# headstage-programmer.net
KiCad netlist of a schematic drawn in EAGLE
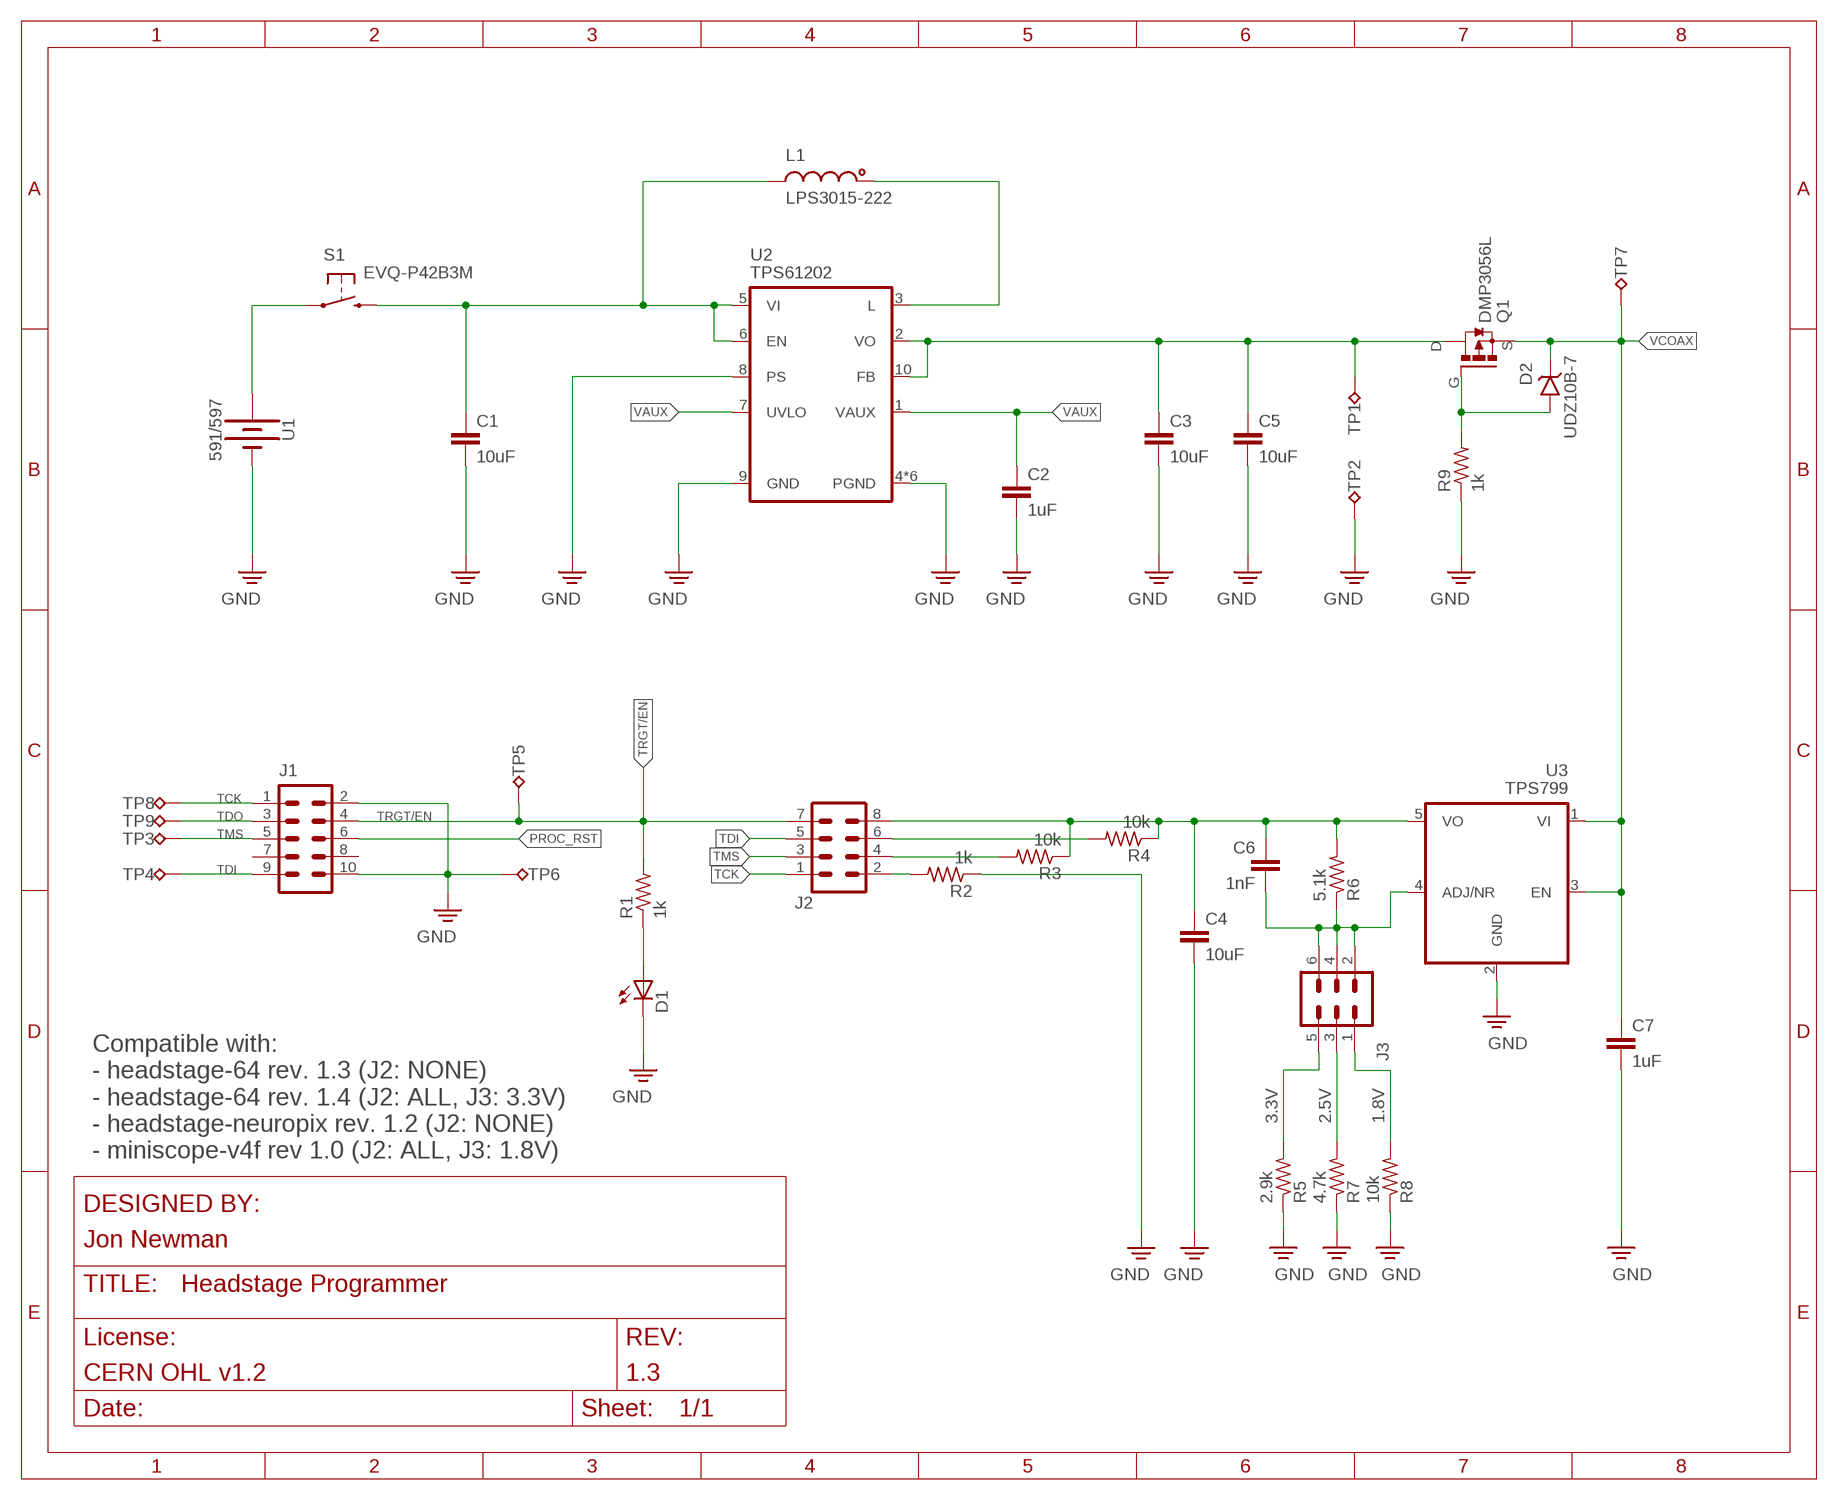
[diagram p0: schematic, sheet 1]

(export (version "E")
  (design (tool "Eeschema 10.0.6"))
  (components
    (comp (ref "C1")
      (value "10uF")
      (footprint "eagle-import:0805")
      (fields (field (name "PARTNO") "C2012X5R1Cxxxxxxx"))
      (libsource (lib "eagle-import") (part "C_0805"))
    )
    (comp (ref "C2")
      (value "1uF")
      (footprint "eagle-import:0603")
      (libsource (lib "eagle-import") (part "C_0603"))
    )
    (comp (ref "C3")
      (value "10uF")
      (footprint "eagle-import:0805")
      (fields (field (name "PARTNO") "C2012X5R1Cxxxxxxx"))
      (libsource (lib "eagle-import") (part "C_0805"))
    )
    (comp (ref "C4")
      (value "10uF")
      (footprint "eagle-import:0805")
      (fields (field (name "PARTNO") "C2012X5R1Cxxxxxxx"))
      (libsource (lib "eagle-import") (part "C_0805"))
    )
    (comp (ref "C5")
      (value "10uF")
      (footprint "eagle-import:0805")
      (fields (field (name "PARTNO") "C2012X5R1Cxxxxxxx"))
      (libsource (lib "eagle-import") (part "C_0805"))
    )
    (comp (ref "C6")
      (value "1nF")
      (footprint "eagle-import:0402")
      (libsource (lib "eagle-import") (part "C_0402"))
    )
    (comp (ref "C7")
      (value "1uF")
      (footprint "eagle-import:0603")
      (libsource (lib "eagle-import") (part "C_0603"))
    )
    (comp (ref "D1")
      (value "LED_0603")
      (footprint "eagle-import:LED-0603")
      (libsource (lib "eagle-import") (part "LED_0603"))
    )
    (comp (ref "D2")
      (value "UDZ10B-7")
      (footprint "eagle-import:SOD-323")
      (libsource (lib "eagle-import") (part "Z-DIODE_SOD-323"))
    )
    (comp (ref "J1")
      (value "302-S101")
      (footprint "eagle-import:2X05_IDC")
      (libsource (lib "eagle-import") (part "PINHD-2X5_IDC"))
    )
    (comp (ref "J2")
      (value "PINHD-2X4_0.05\"")
      (footprint "eagle-import:2X04-0.05_")
      (libsource (lib "eagle-import") (part "PINHD-2X4_0.05{dblquote}"))
    )
    (comp (ref "J3")
      (value "PINHD-2X3_0.05\"")
      (footprint "eagle-import:2X03-0.05_")
      (libsource (lib "eagle-import") (part "PINHD-2X3_0.05{dblquote}"))
    )
    (comp (ref "L1")
      (value "LPS3015-222")
      (footprint "eagle-import:LPS3015")
      (libsource (lib "eagle-import") (part "L_LPS3015"))
    )
    (comp (ref "Q1")
      (value "DMP3056L")
      (footprint "eagle-import:SOT23-GSD")
      (fields (field (name "PARTNO") "DMP3056L-7"))
      (libsource (lib "eagle-import") (part "P-MOSFET_SOT23-GSD"))
    )
    (comp (ref "R1")
      (value "1k")
      (footprint "eagle-import:0402")
      (libsource (lib "eagle-import") (part "R_0402"))
    )
    (comp (ref "R2")
      (value "1k")
      (footprint "eagle-import:0402")
      (libsource (lib "eagle-import") (part "R_0402"))
    )
    (comp (ref "R3")
      (value "10k")
      (footprint "eagle-import:0402")
      (libsource (lib "eagle-import") (part "R_0402"))
    )
    (comp (ref "R4")
      (value "10k")
      (footprint "eagle-import:0402")
      (libsource (lib "eagle-import") (part "R_0402"))
    )
    (comp (ref "R5")
      (value "2.9k")
      (footprint "eagle-import:0402")
      (libsource (lib "eagle-import") (part "R_0402"))
    )
    (comp (ref "R6")
      (value "5.1k")
      (footprint "eagle-import:0402")
      (libsource (lib "eagle-import") (part "R_0402"))
    )
    (comp (ref "R7")
      (value "4.7k")
      (footprint "eagle-import:0402")
      (libsource (lib "eagle-import") (part "R_0402"))
    )
    (comp (ref "R8")
      (value "10k")
      (footprint "eagle-import:0402")
      (libsource (lib "eagle-import") (part "R_0402"))
    )
    (comp (ref "R9")
      (value "1k")
      (footprint "eagle-import:0402")
      (libsource (lib "eagle-import") (part "R_0402"))
    )
    (comp (ref "S1")
      (value "EVQ-P42B3M")
      (footprint "eagle-import:EVQP4")
      (libsource (lib "eagle-import") (part "SPST_TACT2_EVQP4"))
    )
    (comp (ref "TP1")
      (value "TP_1MM")
      (footprint "eagle-import:TESTPOINT_1MM")
      (libsource (lib "eagle-import") (part "TP_1MM"))
    )
    (comp (ref "TP2")
      (value "TP_1MM")
      (footprint "eagle-import:TESTPOINT_1MM")
      (libsource (lib "eagle-import") (part "TP_1MM"))
    )
    (comp (ref "TP3")
      (value "TP_S500-6350-P2")
      (footprint "eagle-import:POGO_S500-6350-P2")
      (libsource (lib "eagle-import") (part "TP_S500-6350-P2"))
    )
    (comp (ref "TP4")
      (value "TP_S500-6350-P2")
      (footprint "eagle-import:POGO_S500-6350-P2")
      (libsource (lib "eagle-import") (part "TP_S500-6350-P2"))
    )
    (comp (ref "TP5")
      (value "TP_S500-6350-P2")
      (footprint "eagle-import:POGO_S500-6350-P2")
      (libsource (lib "eagle-import") (part "TP_S500-6350-P2"))
    )
    (comp (ref "TP6")
      (value "TP_S500-6350-P2")
      (footprint "eagle-import:POGO_S500-6350-P2")
      (libsource (lib "eagle-import") (part "TP_S500-6350-P2"))
    )
    (comp (ref "TP7")
      (value "TP_S500-6350-P2")
      (footprint "eagle-import:POGO_S500-6350-P2")
      (libsource (lib "eagle-import") (part "TP_S500-6350-P2"))
    )
    (comp (ref "TP8")
      (value "TP_S500-6350-P2")
      (footprint "eagle-import:POGO_S500-6350-P2")
      (libsource (lib "eagle-import") (part "TP_S500-6350-P2"))
    )
    (comp (ref "TP9")
      (value "TP_S500-6350-P2")
      (footprint "eagle-import:POGO_S500-6350-P2")
      (libsource (lib "eagle-import") (part "TP_S500-6350-P2"))
    )
    (comp (ref "U1")
      (value "591/597")
      (footprint "eagle-import:597_591_AAA-HOLDER")
      (libsource (lib "eagle-import") (part "BATTERY_597/591"))
    )
    (comp (ref "U2")
      (value "TPS61202")
      (footprint "eagle-import:PWSON-N10+4-3X3")
      (libsource (lib "eagle-import") (part "TPS61200"))
    )
    (comp (ref "U3")
      (value "TPS799")
      (footprint "eagle-import:SOT-23-5")
      (libsource (lib "eagle-import") (part "LDO_ADJUST_TPS799"))
    )
  )
  (nets
    (net (code "1") (name "/TDO") (class "Default")
      (node (ref "J1") (pin "3") (pinfunction "3_3") (pintype "passive"))
      (node (ref "TP9") (pin "P$1") (pinfunction "TP_P$1") (pintype "bidirectional"))
    )
    (net (code "2") (name "GND") (class "Default")
      (node (ref "C1") (pin "2") (pinfunction "2_2") (pintype "passive"))
      (node (ref "C2") (pin "2") (pinfunction "2_2") (pintype "passive"))
      (node (ref "C3") (pin "2") (pinfunction "2_2") (pintype "passive"))
      (node (ref "C4") (pin "2") (pinfunction "2_2") (pintype "passive"))
      (node (ref "C5") (pin "2") (pinfunction "2_2") (pintype "passive"))
      (node (ref "C7") (pin "2") (pinfunction "2_2") (pintype "passive"))
      (node (ref "D1") (pin "C") (pinfunction "C_C") (pintype "passive"))
      (node (ref "J1") (pin "10") (pinfunction "10_10") (pintype "passive"))
      (node (ref "J1") (pin "2") (pinfunction "2_2") (pintype "passive"))
      (node (ref "R2") (pin "1") (pinfunction "1_1") (pintype "passive"))
      (node (ref "R5") (pin "1") (pinfunction "1_1") (pintype "passive"))
      (node (ref "R7") (pin "1") (pinfunction "1_1") (pintype "passive"))
      (node (ref "R8") (pin "1") (pinfunction "1_1") (pintype "passive"))
      (node (ref "R9") (pin "1") (pinfunction "1_1") (pintype "passive"))
      (node (ref "TP2") (pin "1") (pinfunction "TP_1") (pintype "bidirectional"))
      (node (ref "TP6") (pin "P$1") (pinfunction "TP_P$1") (pintype "bidirectional"))
      (node (ref "U1") (pin "-1") (pinfunction "-_-1") (pintype "power_in"))
      (node (ref "U1") (pin "-2") (pinfunction "-_-2") (pintype "power_in"))
      (node (ref "U1") (pin "-3") (pinfunction "-_-3") (pintype "power_in"))
      (node (ref "U2") (pin "4") (pinfunction "PGND_4") (pintype "power_in"))
      (node (ref "U2") (pin "8") (pinfunction "PS_8") (pintype "input"))
      (node (ref "U2") (pin "9") (pinfunction "GND_9") (pintype "power_in"))
      (node (ref "U2") (pin "PAD") (pinfunction "PGND_PAD") (pintype "power_in"))
      (node (ref "U2") (pin "PAD1") (pinfunction "PGND_PAD1") (pintype "power_in"))
      (node (ref "U2") (pin "PAD2") (pinfunction "PGND_PAD2") (pintype "power_in"))
      (node (ref "U2") (pin "PAD3") (pinfunction "PGND_PAD3") (pintype "power_in"))
      (node (ref "U2") (pin "PAD4") (pinfunction "PGND_PAD4") (pintype "power_in"))
      (node (ref "U3") (pin "2") (pinfunction "GND_2") (pintype "power_in"))
    )
    (net (code "3") (name "Net-(D1-PadA)") (class "Default")
      (node (ref "D1") (pin "A") (pinfunction "A_A") (pintype "passive"))
      (node (ref "R1") (pin "1") (pinfunction "1_1") (pintype "passive"))
    )
    (net (code "4") (name "Net-(D2-PadA)") (class "Default")
      (node (ref "D2") (pin "A") (pinfunction "A_A") (pintype "passive"))
      (node (ref "Q1") (pin "G") (pinfunction "G_G") (pintype "bidirectional"))
      (node (ref "R9") (pin "2") (pinfunction "2_2") (pintype "passive"))
    )
    (net (code "5") (name "Net-(J2-Pad2)") (class "Default")
      (node (ref "J2") (pin "2") (pinfunction "2_2") (pintype "passive"))
      (node (ref "R2") (pin "2") (pinfunction "2_2") (pintype "passive"))
    )
    (net (code "6") (name "Net-(J2-Pad4)") (class "Default")
      (node (ref "J2") (pin "4") (pinfunction "4_4") (pintype "passive"))
      (node (ref "R3") (pin "2") (pinfunction "2_2") (pintype "passive"))
    )
    (net (code "7") (name "Net-(J2-Pad6)") (class "Default")
      (node (ref "J2") (pin "6") (pinfunction "6_6") (pintype "passive"))
      (node (ref "R4") (pin "2") (pinfunction "2_2") (pintype "passive"))
    )
    (net (code "8") (name "Net-(J3-Pad1)") (class "Default")
      (node (ref "J3") (pin "1") (pinfunction "1_1") (pintype "passive"))
      (node (ref "R8") (pin "2") (pinfunction "2_2") (pintype "passive"))
    )
    (net (code "9") (name "Net-(J3-Pad3)") (class "Default")
      (node (ref "J3") (pin "3") (pinfunction "3_3") (pintype "passive"))
      (node (ref "R7") (pin "2") (pinfunction "2_2") (pintype "passive"))
    )
    (net (code "10") (name "Net-(J3-Pad5)") (class "Default")
      (node (ref "J3") (pin "5") (pinfunction "5_5") (pintype "passive"))
      (node (ref "R5") (pin "2") (pinfunction "2_2") (pintype "passive"))
    )
    (net (code "11") (name "Net-(S1-P)") (class "Default")
      (node (ref "S1") (pin "1") (pinfunction "P_1") (pintype "passive"))
      (node (ref "U1") (pin "+1") (pinfunction "+_+1") (pintype "power_in"))
      (node (ref "U1") (pin "+2") (pinfunction "+_+2") (pintype "power_in"))
      (node (ref "U1") (pin "+3") (pinfunction "+_+3") (pintype "power_in"))
    )
    (net (code "12") (name "Net-(S1-S)") (class "Default")
      (node (ref "C1") (pin "1") (pinfunction "1_1") (pintype "passive"))
      (node (ref "L1") (pin "2") (pinfunction "2_2") (pintype "passive"))
      (node (ref "S1") (pin "2") (pinfunction "S_2") (pintype "passive"))
      (node (ref "U2") (pin "5") (pinfunction "VI_5") (pintype "power_in"))
      (node (ref "U2") (pin "6") (pinfunction "EN_6") (pintype "input"))
    )
    (net (code "13") (name "Net-(TP1-TP)") (class "Default")
      (node (ref "C3") (pin "1") (pinfunction "1_1") (pintype "passive"))
      (node (ref "C5") (pin "1") (pinfunction "1_1") (pintype "passive"))
      (node (ref "Q1") (pin "D") (pinfunction "D_D") (pintype "bidirectional"))
      (node (ref "TP1") (pin "1") (pinfunction "TP_1") (pintype "bidirectional"))
      (node (ref "U2") (pin "10") (pinfunction "FB_10") (pintype "input"))
      (node (ref "U2") (pin "2") (pinfunction "VO_2") (pintype "power_in"))
    )
    (net (code "14") (name "Net-(U2-L)") (class "Default")
      (node (ref "L1") (pin "1") (pinfunction "1_1") (pintype "passive"))
      (node (ref "U2") (pin "3") (pinfunction "L_3") (pintype "bidirectional"))
    )
    (net (code "15") (name "Net-(U3-ADJ{slash}NR)") (class "Default")
      (node (ref "C6") (pin "2") (pinfunction "2_2") (pintype "passive"))
      (node (ref "J3") (pin "2") (pinfunction "2_2") (pintype "passive"))
      (node (ref "J3") (pin "4") (pinfunction "4_4") (pintype "passive"))
      (node (ref "J3") (pin "6") (pinfunction "6_6") (pintype "passive"))
      (node (ref "R6") (pin "1") (pinfunction "1_1") (pintype "passive"))
      (node (ref "U3") (pin "4") (pinfunction "ADJ/NR_4") (pintype "input"))
    )
    (net (code "16") (name "Net-(U3-VO)") (class "Default")
      (node (ref "C4") (pin "1") (pinfunction "1_1") (pintype "passive"))
      (node (ref "C6") (pin "1") (pinfunction "1_1") (pintype "passive"))
      (node (ref "J2") (pin "8") (pinfunction "8_8") (pintype "passive"))
      (node (ref "R3") (pin "1") (pinfunction "1_1") (pintype "passive"))
      (node (ref "R4") (pin "1") (pinfunction "1_1") (pintype "passive"))
      (node (ref "R6") (pin "2") (pinfunction "2_2") (pintype "passive"))
      (node (ref "U3") (pin "5") (pinfunction "VO_5") (pintype "power_in"))
    )
    (net (code "17") (name "PROC_RST") (class "Default")
      (node (ref "J1") (pin "6") (pinfunction "6_6") (pintype "passive"))
    )
    (net (code "18") (name "TCK") (class "Default")
      (node (ref "J1") (pin "1") (pinfunction "1_1") (pintype "passive"))
      (node (ref "J2") (pin "1") (pinfunction "1_1") (pintype "passive"))
      (node (ref "TP8") (pin "P$1") (pinfunction "TP_P$1") (pintype "bidirectional"))
    )
    (net (code "19") (name "TDI") (class "Default")
      (node (ref "J1") (pin "9") (pinfunction "9_9") (pintype "passive"))
      (node (ref "J2") (pin "5") (pinfunction "5_5") (pintype "passive"))
      (node (ref "TP4") (pin "P$1") (pinfunction "TP_P$1") (pintype "bidirectional"))
    )
    (net (code "20") (name "TMS") (class "Default")
      (node (ref "J1") (pin "5") (pinfunction "5_5") (pintype "passive"))
      (node (ref "J2") (pin "3") (pinfunction "3_3") (pintype "passive"))
      (node (ref "TP3") (pin "P$1") (pinfunction "TP_P$1") (pintype "bidirectional"))
    )
    (net (code "21") (name "TRGT{slash}EN") (class "Default")
      (node (ref "J1") (pin "4") (pinfunction "4_4") (pintype "passive"))
      (node (ref "J2") (pin "7") (pinfunction "7_7") (pintype "passive"))
      (node (ref "R1") (pin "2") (pinfunction "2_2") (pintype "passive"))
      (node (ref "TP5") (pin "P$1") (pinfunction "TP_P$1") (pintype "bidirectional"))
    )
    (net (code "22") (name "VAUX") (class "Default")
      (node (ref "C2") (pin "1") (pinfunction "1_1") (pintype "passive"))
      (node (ref "U2") (pin "1") (pinfunction "VAUX_1") (pintype "output"))
      (node (ref "U2") (pin "7") (pinfunction "UVLO_7") (pintype "passive"))
    )
    (net (code "23") (name "VCOAX") (class "Default")
      (node (ref "C7") (pin "1") (pinfunction "1_1") (pintype "passive"))
      (node (ref "D2") (pin "C") (pinfunction "C_C") (pintype "passive"))
      (node (ref "Q1") (pin "S") (pinfunction "S_S") (pintype "bidirectional"))
      (node (ref "TP7") (pin "P$1") (pinfunction "TP_P$1") (pintype "bidirectional"))
      (node (ref "U3") (pin "1") (pinfunction "VI_1") (pintype "power_in"))
      (node (ref "U3") (pin "3") (pinfunction "EN_3") (pintype "input"))
    )
    (net (code "24") (name "unconnected-(J1-Pad7)") (class "Default")
      (node (ref "J1") (pin "7") (pinfunction "7_7") (pintype "passive"))
    )
    (net (code "25") (name "unconnected-(J1-Pad8)") (class "Default")
      (node (ref "J1") (pin "8") (pinfunction "8_8") (pintype "passive"))
    )
  )
)
